# ATMEGA2560-Schematic.net
KiCad netlist of a schematic drawn in Altium Designer
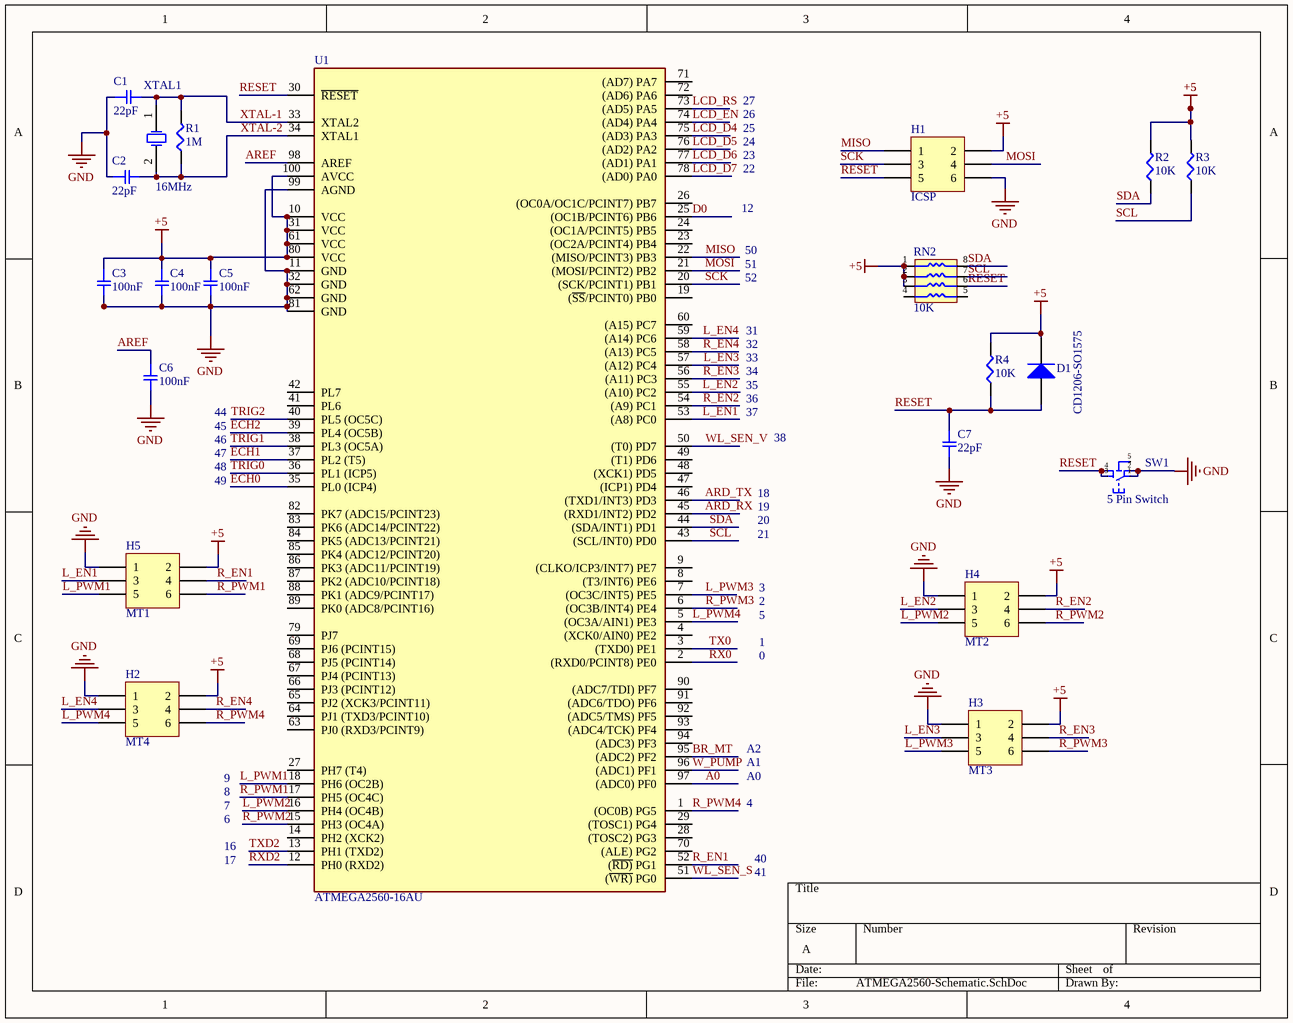
[diagram p0: ATMEGA2560-Schematic.SchDoc]

(export (version "E")
  (design (tool "Eeschema 10.0.6"))
  (components
    (comp (ref "C1")
      (value "22pF")
      (description "CAP CER 10000PF 250V X7T 0805")
      (fields
        (field (name "DIGI-KEY PART NUMBER") "490-13986-1-ND")
        (field (name "PART NUMBER") "GC321AD72E103KX01D")
      )
      (libsource (lib "capacitor0805") (part "GC321AD72E103KX01D"))
    )
    (comp (ref "C2")
      (value "22pF")
      (description "CAP CER 10000PF 250V X7T 0805")
      (fields
        (field (name "DIGI-KEY PART NUMBER") "490-13986-1-ND")
        (field (name "PART NUMBER") "GC321AD72E103KX01D")
      )
      (libsource (lib "capacitor0805") (part "GC321AD72E103KX01D"))
    )
    (comp (ref "C3")
      (value "100nF")
      (footprint "SMD-0805C")
      (description "CAP CER 10000PF 250V X7T 0805")
      (fields
        (field (name "DIGI-KEY PART NUMBER") "490-13986-1-ND")
        (field (name "PART NUMBER") "GC321AD72E103KX01D")
      )
      (libsource (lib "capacitor0805") (part "GC321AD72E103KX01D"))
    )
    (comp (ref "C4")
      (value "100nF")
      (footprint "SMD-0805C")
      (description "CAP CER 10000PF 250V X7T 0805")
      (fields
        (field (name "DIGI-KEY PART NUMBER") "490-13986-1-ND")
        (field (name "PART NUMBER") "GC321AD72E103KX01D")
      )
      (libsource (lib "capacitor0805") (part "GC321AD72E103KX01D"))
    )
    (comp (ref "C5")
      (value "100nF")
      (footprint "SMD-0805C")
      (description "CAP CER 10000PF 250V X7T 0805")
      (fields
        (field (name "DIGI-KEY PART NUMBER") "490-13986-1-ND")
        (field (name "PART NUMBER") "GC321AD72E103KX01D")
      )
      (libsource (lib "capacitor0805") (part "GC321AD72E103KX01D"))
    )
    (comp (ref "C6")
      (value "100nF")
      (footprint "SMD-0805C")
      (description "CAP CER 10000PF 250V X7T 0805")
      (fields
        (field (name "DIGI-KEY PART NUMBER") "490-13986-1-ND")
        (field (name "PART NUMBER") "GC321AD72E103KX01D")
      )
      (libsource (lib "capacitor0805") (part "GC321AD72E103KX01D"))
    )
    (comp (ref "C7")
      (value "22pF")
      (footprint "SMD-0603C")
      (description "CAP CER 10000PF 250V X7T 0805")
      (fields
        (field (name "DIGI-KEY PART NUMBER") "490-13986-1-ND")
        (field (name "PART NUMBER") "GC321AD72E103KX01D")
      )
      (libsource (lib "capacitor0805") (part "GC321AD72E103KX01D"))
    )
    (comp (ref "D1")
      (value "CD1206-SO1575")
      (footprint "D1206-RD")
      (description "Default Diode")
      (fields (field (name "PUBLISHER") "Altium Limited"))
      (libsource (lib "Miscellaneous Devices") (part "Diode"))
    )
    (comp (ref "H1")
      (value "ICSP")
      (footprint "HDR2X3")
      (description "Header, 3-Pin, Dual row")
      (fields (field (name "PUBLISHER") "Altium Limited"))
      (libsource (lib "Miscellaneous Connectors") (part "Header 3X2"))
    )
    (comp (ref "H2")
      (value "MT4")
      (footprint "HDR2X3")
      (description "Header, 3-Pin, Dual row")
      (fields (field (name "PUBLISHER") "Altium Limited"))
      (libsource (lib "Miscellaneous Connectors") (part "Header 3X2"))
    )
    (comp (ref "H3")
      (value "MT3")
      (footprint "HDR2X3")
      (description "Header, 3-Pin, Dual row")
      (fields (field (name "PUBLISHER") "Altium Limited"))
      (libsource (lib "Miscellaneous Connectors") (part "Header 3X2"))
    )
    (comp (ref "H4")
      (value "MT2")
      (footprint "HDR2X3")
      (description "Header, 3-Pin, Dual row")
      (fields (field (name "PUBLISHER") "Altium Limited"))
      (libsource (lib "Miscellaneous Connectors") (part "Header 3X2"))
    )
    (comp (ref "H5")
      (value "MT1")
      (footprint "HDR2X3")
      (description "Header, 3-Pin, Dual row")
      (fields (field (name "PUBLISHER") "Altium Limited"))
      (libsource (lib "Miscellaneous Connectors") (part "Header 3X2"))
    )
    (comp (ref "R1")
      (value "1M")
      (footprint "SMD-0805-RES")
      (description "RES SMD 1.1 OHM 1% 1/3W 0805")
      (fields (field (name "PART NUMBER") "ERJ-6BQF1R1V") (field (name "DIGI-KEY PART NUMBER") "P17500CT-ND"))
      (libsource (lib "Res0805") (part "ERJ-6BQF1R1V"))
    )
    (comp (ref "R2")
      (value "10K")
      (description "RES SMD 1.1 OHM 1% 1/3W 0805")
      (fields (field (name "PART NUMBER") "ERJ-6BQF1R1V") (field (name "DIGI-KEY PART NUMBER") "P17500CT-ND"))
      (libsource (lib "Res0805") (part "ERJ-6BQF1R1V"))
    )
    (comp (ref "R3")
      (value "10K")
      (description "RES SMD 1.1 OHM 1% 1/3W 0805")
      (fields (field (name "PART NUMBER") "ERJ-6BQF1R1V") (field (name "DIGI-KEY PART NUMBER") "P17500CT-ND"))
      (libsource (lib "Res0805") (part "ERJ-6BQF1R1V"))
    )
    (comp (ref "R4")
      (value "10K")
      (description "RES SMD 1.1 OHM 1% 1/3W 0805")
      (fields (field (name "PART NUMBER") "ERJ-6BQF1R1V") (field (name "DIGI-KEY PART NUMBER") "P17500CT-ND"))
      (libsource (lib "Res0805") (part "ERJ-6BQF1R1V"))
    )
    (comp (ref "RN2")
      (value "10K")
      (footprint "RA0603-8")
      (fields (field (name "MF") "Yageo") (field (name "MP") "YC164-JR-07330RL"))
      (libsource (lib "ResNetwork(SMD)") (part "RES_NETWORK"))
    )
    (comp (ref "SW1")
      (value "5 Pin Switch")
      (footprint "SPDT-5Pin")
      (libsource (lib "SPDT-SW") (part "SPDT-SWITCH"))
    )
    (comp (ref "U1")
      (value "ATMEGA2560-16AU")
      (footprint "TQFP-100(LCSC)")
      (description "Integrated Circuit")
      (libsource (lib "ATMEGA2560-16AU") (part "ATMEGA2560-16AU (LCSC)"))
    )
    (comp (ref "XTAL1")
      (value "16MHz")
      (description "Crystal Oscillator")
      (fields (field (name "PUBLISHER") "Altium Limited"))
      (libsource (lib "XTAL_Generic") (part "Crystal Oscillator"))
    )
  )
  (nets
    (net (code "1") (name "+5") (class "Default")
      (node (ref "C3") (pin "1") (pinfunction "1_1") (pintype "passive"))
      (node (ref "C4") (pin "1") (pinfunction "1_1") (pintype "passive"))
      (node (ref "C5") (pin "1") (pinfunction "1_1") (pintype "passive"))
      (node (ref "D1") (pin "2") (pinfunction "K_2") (pintype "passive"))
      (node (ref "H1") (pin "2") (pinfunction "2_2") (pintype "passive"))
      (node (ref "H2") (pin "2") (pinfunction "2_2") (pintype "passive"))
      (node (ref "H3") (pin "2") (pinfunction "2_2") (pintype "passive"))
      (node (ref "H4") (pin "2") (pinfunction "2_2") (pintype "passive"))
      (node (ref "H5") (pin "2") (pinfunction "2_2") (pintype "passive"))
      (node (ref "R2") (pin "2") (pinfunction "2_2") (pintype "passive"))
      (node (ref "R3") (pin "2") (pinfunction "2_2") (pintype "passive"))
      (node (ref "R4") (pin "2") (pinfunction "2_2") (pintype "passive"))
      (node (ref "RN2") (pin "1") (pinfunction "1_1") (pintype "passive"))
      (node (ref "RN2") (pin "2") (pinfunction "2_2") (pintype "passive"))
      (node (ref "RN2") (pin "3") (pinfunction "3_3") (pintype "passive"))
      (node (ref "U1") (pin "10") (pinfunction "VCC_10") (pintype "passive"))
      (node (ref "U1") (pin "100") (pinfunction "AVCC_100") (pintype "passive"))
      (node (ref "U1") (pin "31") (pinfunction "VCC_31") (pintype "passive"))
      (node (ref "U1") (pin "61") (pinfunction "VCC_61") (pintype "passive"))
      (node (ref "U1") (pin "80") (pinfunction "VCC_80") (pintype "passive"))
    )
    (net (code "2") (name "/A0") (class "Default")
      (node (ref "U1") (pin "97") (pinfunction "(ADC0)_PF0_97") (pintype "passive"))
    )
    (net (code "3") (name "/ARD_RX") (class "Default")
      (node (ref "U1") (pin "45") (pinfunction "(RXD1/INT2)_PD2_45") (pintype "passive"))
    )
    (net (code "4") (name "/ARD_TX") (class "Default")
      (node (ref "U1") (pin "46") (pinfunction "(TXD1/INT3)_PD3_46") (pintype "passive"))
    )
    (net (code "5") (name "/AREF") (class "Default")
      (node (ref "C6") (pin "1") (pinfunction "1_1") (pintype "passive"))
      (node (ref "U1") (pin "98") (pinfunction "AREF_98") (pintype "passive"))
    )
    (net (code "6") (name "/BR_MT") (class "Default")
      (node (ref "U1") (pin "95") (pinfunction "(ADC2)_PF2_95") (pintype "passive"))
    )
    (net (code "7") (name "/D0") (class "Default")
      (node (ref "U1") (pin "25") (pinfunction "(OC1B/PCINT6)_PB6_25") (pintype "passive"))
    )
    (net (code "8") (name "/ECH0") (class "Default")
      (node (ref "U1") (pin "35") (pinfunction "PL0_(ICP4)_35") (pintype "passive"))
    )
    (net (code "9") (name "/ECH1") (class "Default")
      (node (ref "U1") (pin "37") (pinfunction "PL2_(T5)_37") (pintype "passive"))
    )
    (net (code "10") (name "/ECH2") (class "Default")
      (node (ref "U1") (pin "39") (pinfunction "PL4_(OC5B)_39") (pintype "passive"))
    )
    (net (code "11") (name "/LCD_D4") (class "Default")
      (node (ref "U1") (pin "75") (pinfunction "(AD3)_PA3_75") (pintype "passive"))
    )
    (net (code "12") (name "/LCD_D5") (class "Default")
      (node (ref "U1") (pin "76") (pinfunction "(AD2)_PA2_76") (pintype "passive"))
    )
    (net (code "13") (name "/LCD_D6") (class "Default")
      (node (ref "U1") (pin "77") (pinfunction "(AD1)_PA1_77") (pintype "passive"))
    )
    (net (code "14") (name "/LCD_D7") (class "Default")
      (node (ref "U1") (pin "78") (pinfunction "(AD0)_PA0_78") (pintype "passive"))
    )
    (net (code "15") (name "/LCD_EN") (class "Default")
      (node (ref "U1") (pin "74") (pinfunction "(AD4)_PA4_74") (pintype "passive"))
    )
    (net (code "16") (name "/LCD_RS") (class "Default")
      (node (ref "U1") (pin "73") (pinfunction "(AD5)_PA5_73") (pintype "passive"))
    )
    (net (code "17") (name "/L_EN1") (class "Default")
      (node (ref "H5") (pin "3") (pinfunction "3_3") (pintype "passive"))
      (node (ref "U1") (pin "53") (pinfunction "(A8)_PC0_53") (pintype "passive"))
    )
    (net (code "18") (name "/L_EN2") (class "Default")
      (node (ref "H4") (pin "3") (pinfunction "3_3") (pintype "passive"))
      (node (ref "U1") (pin "55") (pinfunction "(A10)_PC2_55") (pintype "passive"))
    )
    (net (code "19") (name "/L_EN3") (class "Default")
      (node (ref "H3") (pin "3") (pinfunction "3_3") (pintype "passive"))
      (node (ref "U1") (pin "57") (pinfunction "(A12)_PC4_57") (pintype "passive"))
    )
    (net (code "20") (name "/L_EN4") (class "Default")
      (node (ref "H2") (pin "3") (pinfunction "3_3") (pintype "passive"))
      (node (ref "U1") (pin "59") (pinfunction "(A14)_PC6_59") (pintype "passive"))
    )
    (net (code "21") (name "/L_PWM1") (class "Default")
      (node (ref "H5") (pin "5") (pinfunction "5_5") (pintype "passive"))
      (node (ref "U1") (pin "18") (pinfunction "PH6_(OC2B)_18") (pintype "passive"))
    )
    (net (code "22") (name "/L_PWM2") (class "Default")
      (node (ref "H4") (pin "5") (pinfunction "5_5") (pintype "passive"))
      (node (ref "U1") (pin "16") (pinfunction "PH4_(OC4B)_16") (pintype "passive"))
    )
    (net (code "23") (name "/L_PWM3") (class "Default")
      (node (ref "H3") (pin "5") (pinfunction "5_5") (pintype "passive"))
      (node (ref "U1") (pin "7") (pinfunction "(OC3C/INT5)_PE5_7") (pintype "passive"))
    )
    (net (code "24") (name "/L_PWM4") (class "Default")
      (node (ref "H2") (pin "5") (pinfunction "5_5") (pintype "passive"))
      (node (ref "U1") (pin "5") (pinfunction "(OC3A/AIN1)_PE3_5") (pintype "passive"))
    )
    (net (code "25") (name "/MISO") (class "Default")
      (node (ref "H1") (pin "1") (pinfunction "1_1") (pintype "passive"))
      (node (ref "U1") (pin "22") (pinfunction "(MISO/PCINT3)_PB3_22") (pintype "passive"))
    )
    (net (code "26") (name "/MOSI") (class "Default")
      (node (ref "H1") (pin "4") (pinfunction "4_4") (pintype "passive"))
      (node (ref "U1") (pin "21") (pinfunction "(MOSI/PCINT2)_PB2_21") (pintype "passive"))
    )
    (net (code "27") (name "/RESET") (class "Default")
      (node (ref "C7") (pin "1") (pinfunction "1_1") (pintype "passive"))
      (node (ref "D1") (pin "1") (pinfunction "A_1") (pintype "passive"))
      (node (ref "H1") (pin "5") (pinfunction "5_5") (pintype "passive"))
      (node (ref "R4") (pin "1") (pinfunction "1_1") (pintype "passive"))
      (node (ref "RN2") (pin "6") (pinfunction "6_6") (pintype "passive"))
      (node (ref "SW1") (pin "3") (pinfunction "3_3") (pintype "passive"))
      (node (ref "SW1") (pin "4") (pinfunction "4_4") (pintype "passive"))
      (node (ref "U1") (pin "30") (pinfunction "~{RESET}_30") (pintype "passive"))
    )
    (net (code "28") (name "/RX0") (class "Default")
      (node (ref "U1") (pin "2") (pinfunction "(RXD0/PCINT8)_PE0_2") (pintype "passive"))
    )
    (net (code "29") (name "/RXD2") (class "Default")
      (node (ref "U1") (pin "12") (pinfunction "PH0_(RXD2)_12") (pintype "passive"))
    )
    (net (code "30") (name "/R_EN1") (class "Default")
      (node (ref "H5") (pin "4") (pinfunction "4_4") (pintype "passive"))
      (node (ref "U1") (pin "52") (pinfunction "(~{RD)}_PG1_52") (pintype "passive"))
    )
    (net (code "31") (name "/R_EN2") (class "Default")
      (node (ref "H4") (pin "4") (pinfunction "4_4") (pintype "passive"))
      (node (ref "U1") (pin "54") (pinfunction "(A9)_PC1_54") (pintype "passive"))
    )
    (net (code "32") (name "/R_EN3") (class "Default")
      (node (ref "H3") (pin "4") (pinfunction "4_4") (pintype "passive"))
      (node (ref "U1") (pin "56") (pinfunction "(A11)_PC3_56") (pintype "passive"))
    )
    (net (code "33") (name "/R_EN4") (class "Default")
      (node (ref "H2") (pin "4") (pinfunction "4_4") (pintype "passive"))
      (node (ref "U1") (pin "58") (pinfunction "(A13)_PC5_58") (pintype "passive"))
    )
    (net (code "34") (name "/R_PWM1") (class "Default")
      (node (ref "H5") (pin "6") (pinfunction "6_6") (pintype "passive"))
      (node (ref "U1") (pin "17") (pinfunction "PH5_(OC4C)_17") (pintype "passive"))
    )
    (net (code "35") (name "/R_PWM2") (class "Default")
      (node (ref "H4") (pin "6") (pinfunction "6_6") (pintype "passive"))
      (node (ref "U1") (pin "15") (pinfunction "PH3_(OC4A)_15") (pintype "passive"))
    )
    (net (code "36") (name "/R_PWM3") (class "Default")
      (node (ref "H3") (pin "6") (pinfunction "6_6") (pintype "passive"))
      (node (ref "U1") (pin "6") (pinfunction "(OC3B/INT4)_PE4_6") (pintype "passive"))
    )
    (net (code "37") (name "/R_PWM4") (class "Default")
      (node (ref "H2") (pin "6") (pinfunction "6_6") (pintype "passive"))
      (node (ref "U1") (pin "1") (pinfunction "(OC0B)_PG5_1") (pintype "passive"))
    )
    (net (code "38") (name "/SCK") (class "Default")
      (node (ref "H1") (pin "3") (pinfunction "3_3") (pintype "passive"))
      (node (ref "U1") (pin "20") (pinfunction "(SCK/PCINT1)_PB1_20") (pintype "passive"))
    )
    (net (code "39") (name "/SCL") (class "Default")
      (node (ref "R3") (pin "1") (pinfunction "1_1") (pintype "passive"))
      (node (ref "RN2") (pin "7") (pinfunction "7_7") (pintype "passive"))
      (node (ref "U1") (pin "43") (pinfunction "(SCL/INT0)_PD0_43") (pintype "passive"))
    )
    (net (code "40") (name "/SDA") (class "Default")
      (node (ref "R2") (pin "1") (pinfunction "1_1") (pintype "passive"))
      (node (ref "RN2") (pin "8") (pinfunction "8_8") (pintype "passive"))
      (node (ref "U1") (pin "44") (pinfunction "(SDA/INT1)_PD1_44") (pintype "passive"))
    )
    (net (code "41") (name "/TRIG0") (class "Default")
      (node (ref "U1") (pin "36") (pinfunction "PL1_(ICP5)_36") (pintype "passive"))
    )
    (net (code "42") (name "/TRIG1") (class "Default")
      (node (ref "U1") (pin "38") (pinfunction "PL3_(OC5A)_38") (pintype "passive"))
    )
    (net (code "43") (name "/TRIG2") (class "Default")
      (node (ref "U1") (pin "40") (pinfunction "PL5_(OC5C)_40") (pintype "passive"))
    )
    (net (code "44") (name "/TX0") (class "Default")
      (node (ref "U1") (pin "3") (pinfunction "(TXD0)_PE1_3") (pintype "passive"))
    )
    (net (code "45") (name "/TXD2") (class "Default")
      (node (ref "U1") (pin "13") (pinfunction "PH1_(TXD2)_13") (pintype "passive"))
    )
    (net (code "46") (name "/WL_SEN_S") (class "Default")
      (node (ref "U1") (pin "51") (pinfunction "(~{WR)}_PG0_51") (pintype "passive"))
    )
    (net (code "47") (name "/WL_SEN_V") (class "Default")
      (node (ref "U1") (pin "50") (pinfunction "(T0)_PD7_50") (pintype "passive"))
    )
    (net (code "48") (name "/W_PUMP") (class "Default")
      (node (ref "U1") (pin "96") (pinfunction "(ADC1)_PF1_96") (pintype "passive"))
    )
    (net (code "49") (name "/XTAL-1") (class "Default")
      (node (ref "C1") (pin "2") (pinfunction "2_2") (pintype "passive"))
      (node (ref "R1") (pin "2") (pinfunction "2_2") (pintype "passive"))
      (node (ref "U1") (pin "33") (pinfunction "XTAL2_33") (pintype "passive"))
      (node (ref "XTAL1") (pin "1") (pinfunction "OSC1_1") (pintype "passive"))
    )
    (net (code "50") (name "/XTAL-2") (class "Default")
      (node (ref "C2") (pin "2") (pinfunction "2_2") (pintype "passive"))
      (node (ref "R1") (pin "1") (pinfunction "1_1") (pintype "passive"))
      (node (ref "U1") (pin "34") (pinfunction "XTAL1_34") (pintype "passive"))
      (node (ref "XTAL1") (pin "2") (pinfunction "OSC2_2") (pintype "passive"))
    )
    (net (code "51") (name "GND") (class "Default")
      (node (ref "C1") (pin "1") (pinfunction "1_1") (pintype "passive"))
      (node (ref "C2") (pin "1") (pinfunction "1_1") (pintype "passive"))
      (node (ref "C3") (pin "2") (pinfunction "2_2") (pintype "passive"))
      (node (ref "C4") (pin "2") (pinfunction "2_2") (pintype "passive"))
      (node (ref "C5") (pin "2") (pinfunction "2_2") (pintype "passive"))
      (node (ref "C6") (pin "2") (pinfunction "2_2") (pintype "passive"))
      (node (ref "C7") (pin "2") (pinfunction "2_2") (pintype "passive"))
      (node (ref "H1") (pin "6") (pinfunction "6_6") (pintype "passive"))
      (node (ref "H2") (pin "1") (pinfunction "1_1") (pintype "passive"))
      (node (ref "H3") (pin "1") (pinfunction "1_1") (pintype "passive"))
      (node (ref "H4") (pin "1") (pinfunction "1_1") (pintype "passive"))
      (node (ref "H5") (pin "1") (pinfunction "1_1") (pintype "passive"))
      (node (ref "SW1") (pin "1") (pinfunction "1_1") (pintype "passive"))
      (node (ref "SW1") (pin "2") (pinfunction "2_2") (pintype "passive"))
      (node (ref "U1") (pin "11") (pinfunction "GND_11") (pintype "passive"))
      (node (ref "U1") (pin "32") (pinfunction "GND_32") (pintype "passive"))
      (node (ref "U1") (pin "62") (pinfunction "GND_62") (pintype "passive"))
      (node (ref "U1") (pin "81") (pinfunction "GND_81") (pintype "passive"))
      (node (ref "U1") (pin "99") (pinfunction "AGND_99") (pintype "passive"))
    )
    (net (code "52") (name "unconnected-(RN2-Pad4)") (class "Default")
      (node (ref "RN2") (pin "4") (pinfunction "4_4") (pintype "passive"))
    )
    (net (code "53") (name "unconnected-(RN2-Pad5)") (class "Default")
      (node (ref "RN2") (pin "5") (pinfunction "5_5") (pintype "passive"))
    )
    (net (code "54") (name "unconnected-(SW1-Pad5)") (class "Default")
      (node (ref "SW1") (pin "5") (pinfunction "5_5") (pintype "passive"))
    )
    (net (code "55") (name "unconnected-(U1-(A15)_PC7-Pad60)") (class "Default")
      (node (ref "U1") (pin "60") (pinfunction "(A15)_PC7_60") (pintype "passive"))
    )
    (net (code "56") (name "unconnected-(U1-(AD6)_PA6-Pad72)") (class "Default")
      (node (ref "U1") (pin "72") (pinfunction "(AD6)_PA6_72") (pintype "passive"))
    )
    (net (code "57") (name "unconnected-(U1-(AD7)_PA7-Pad71)") (class "Default")
      (node (ref "U1") (pin "71") (pinfunction "(AD7)_PA7_71") (pintype "passive"))
    )
    (net (code "58") (name "unconnected-(U1-(ADC3)_PF3-Pad94)") (class "Default")
      (node (ref "U1") (pin "94") (pinfunction "(ADC3)_PF3_94") (pintype "passive"))
    )
    (net (code "59") (name "unconnected-(U1-(ADC4{slash}TCK)_PF4-Pad93)") (class "Default")
      (node (ref "U1") (pin "93") (pinfunction "(ADC4/TCK)_PF4_93") (pintype "passive"))
    )
    (net (code "60") (name "unconnected-(U1-(ADC5{slash}TMS)_PF5-Pad92)") (class "Default")
      (node (ref "U1") (pin "92") (pinfunction "(ADC5/TMS)_PF5_92") (pintype "passive"))
    )
    (net (code "61") (name "unconnected-(U1-(ADC6{slash}TDO)_PF6-Pad91)") (class "Default")
      (node (ref "U1") (pin "91") (pinfunction "(ADC6/TDO)_PF6_91") (pintype "passive"))
    )
    (net (code "62") (name "unconnected-(U1-(ADC7{slash}TDI)_PF7-Pad90)") (class "Default")
      (node (ref "U1") (pin "90") (pinfunction "(ADC7/TDI)_PF7_90") (pintype "passive"))
    )
    (net (code "63") (name "unconnected-(U1-(ALE)_PG2-Pad70)") (class "Default")
      (node (ref "U1") (pin "70") (pinfunction "(ALE)_PG2_70") (pintype "passive"))
    )
    (net (code "64") (name "unconnected-(U1-(CLKO{slash}ICP3{slash}INT7)_PE7-Pad9)") (class "Default")
      (node (ref "U1") (pin "9") (pinfunction "(CLKO/ICP3/INT7)_PE7_9") (pintype "passive"))
    )
    (net (code "65") (name "unconnected-(U1-(ICP1)_PD4-Pad47)") (class "Default")
      (node (ref "U1") (pin "47") (pinfunction "(ICP1)_PD4_47") (pintype "passive"))
    )
    (net (code "66") (name "unconnected-(U1-(OC0A{slash}OC1C{slash}PCINT7)_PB7-Pad26)") (class "Default")
      (node (ref "U1") (pin "26") (pinfunction "(OC0A/OC1C/PCINT7)_PB7_26") (pintype "passive"))
    )
    (net (code "67") (name "unconnected-(U1-(OC1A{slash}PCINT5)_PB5-Pad24)") (class "Default")
      (node (ref "U1") (pin "24") (pinfunction "(OC1A/PCINT5)_PB5_24") (pintype "passive"))
    )
    (net (code "68") (name "unconnected-(U1-(OC2A{slash}PCINT4)_PB4-Pad23)") (class "Default")
      (node (ref "U1") (pin "23") (pinfunction "(OC2A/PCINT4)_PB4_23") (pintype "passive"))
    )
    (net (code "69") (name "unconnected-(U1-(T1)_PD6-Pad49)") (class "Default")
      (node (ref "U1") (pin "49") (pinfunction "(T1)_PD6_49") (pintype "passive"))
    )
    (net (code "70") (name "unconnected-(U1-(T3{slash}INT6)_PE6-Pad8)") (class "Default")
      (node (ref "U1") (pin "8") (pinfunction "(T3/INT6)_PE6_8") (pintype "passive"))
    )
    (net (code "71") (name "unconnected-(U1-(TOSC1)_PG4-Pad29)") (class "Default")
      (node (ref "U1") (pin "29") (pinfunction "(TOSC1)_PG4_29") (pintype "passive"))
    )
    (net (code "72") (name "unconnected-(U1-(TOSC2)_PG3-Pad28)") (class "Default")
      (node (ref "U1") (pin "28") (pinfunction "(TOSC2)_PG3_28") (pintype "passive"))
    )
    (net (code "73") (name "unconnected-(U1-(XCK0{slash}AIN0)_PE2-Pad4)") (class "Default")
      (node (ref "U1") (pin "4") (pinfunction "(XCK0/AIN0)_PE2_4") (pintype "passive"))
    )
    (net (code "74") (name "unconnected-(U1-(XCK1)_PD5-Pad48)") (class "Default")
      (node (ref "U1") (pin "48") (pinfunction "(XCK1)_PD5_48") (pintype "passive"))
    )
    (net (code "75") (name "unconnected-(U1-(~{SS}{slash}PCINT0)_PB0-Pad19)") (class "Default")
      (node (ref "U1") (pin "19") (pinfunction "(~{SS}/PCINT0)_PB0_19") (pintype "passive"))
    )
    (net (code "76") (name "unconnected-(U1-PH2_(XCK2)-Pad14)") (class "Default")
      (node (ref "U1") (pin "14") (pinfunction "PH2_(XCK2)_14") (pintype "passive"))
    )
    (net (code "77") (name "unconnected-(U1-PH7_(T4)-Pad27)") (class "Default")
      (node (ref "U1") (pin "27") (pinfunction "PH7_(T4)_27") (pintype "passive"))
    )
    (net (code "78") (name "unconnected-(U1-PJ0_(RXD3{slash}PCINT9)-Pad63)") (class "Default")
      (node (ref "U1") (pin "63") (pinfunction "PJ0_(RXD3/PCINT9)_63") (pintype "passive"))
    )
    (net (code "79") (name "unconnected-(U1-PJ1_(TXD3{slash}PCINT10)-Pad64)") (class "Default")
      (node (ref "U1") (pin "64") (pinfunction "PJ1_(TXD3/PCINT10)_64") (pintype "passive"))
    )
    (net (code "80") (name "unconnected-(U1-PJ2_(XCK3{slash}PCINT11)-Pad65)") (class "Default")
      (node (ref "U1") (pin "65") (pinfunction "PJ2_(XCK3/PCINT11)_65") (pintype "passive"))
    )
    (net (code "81") (name "unconnected-(U1-PJ3_(PCINT12)-Pad66)") (class "Default")
      (node (ref "U1") (pin "66") (pinfunction "PJ3_(PCINT12)_66") (pintype "passive"))
    )
    (net (code "82") (name "unconnected-(U1-PJ4_(PCINT13)-Pad67)") (class "Default")
      (node (ref "U1") (pin "67") (pinfunction "PJ4_(PCINT13)_67") (pintype "passive"))
    )
    (net (code "83") (name "unconnected-(U1-PJ5_(PCINT14)-Pad68)") (class "Default")
      (node (ref "U1") (pin "68") (pinfunction "PJ5_(PCINT14)_68") (pintype "passive"))
    )
    (net (code "84") (name "unconnected-(U1-PJ6_(PCINT15)-Pad69)") (class "Default")
      (node (ref "U1") (pin "69") (pinfunction "PJ6_(PCINT15)_69") (pintype "passive"))
    )
    (net (code "85") (name "unconnected-(U1-PJ7-Pad79)") (class "Default")
      (node (ref "U1") (pin "79") (pinfunction "PJ7_79") (pintype "passive"))
    )
    (net (code "86") (name "unconnected-(U1-PK0_(ADC8{slash}PCINT16)-Pad89)") (class "Default")
      (node (ref "U1") (pin "89") (pinfunction "PK0_(ADC8/PCINT16)_89") (pintype "passive"))
    )
    (net (code "87") (name "unconnected-(U1-PK1_(ADC9{slash}PCINT17)-Pad88)") (class "Default")
      (node (ref "U1") (pin "88") (pinfunction "PK1_(ADC9/PCINT17)_88") (pintype "passive"))
    )
    (net (code "88") (name "unconnected-(U1-PK2_(ADC10{slash}PCINT18)-Pad87)") (class "Default")
      (node (ref "U1") (pin "87") (pinfunction "PK2_(ADC10/PCINT18)_87") (pintype "passive"))
    )
    (net (code "89") (name "unconnected-(U1-PK3_(ADC11{slash}PCINT19)-Pad86)") (class "Default")
      (node (ref "U1") (pin "86") (pinfunction "PK3_(ADC11/PCINT19)_86") (pintype "passive"))
    )
    (net (code "90") (name "unconnected-(U1-PK4_(ADC12{slash}PCINT20)-Pad85)") (class "Default")
      (node (ref "U1") (pin "85") (pinfunction "PK4_(ADC12/PCINT20)_85") (pintype "passive"))
    )
    (net (code "91") (name "unconnected-(U1-PK5_(ADC13{slash}PCINT21)-Pad84)") (class "Default")
      (node (ref "U1") (pin "84") (pinfunction "PK5_(ADC13/PCINT21)_84") (pintype "passive"))
    )
    (net (code "92") (name "unconnected-(U1-PK6_(ADC14{slash}PCINT22)-Pad83)") (class "Default")
      (node (ref "U1") (pin "83") (pinfunction "PK6_(ADC14/PCINT22)_83") (pintype "passive"))
    )
    (net (code "93") (name "unconnected-(U1-PK7_(ADC15{slash}PCINT23)-Pad82)") (class "Default")
      (node (ref "U1") (pin "82") (pinfunction "PK7_(ADC15/PCINT23)_82") (pintype "passive"))
    )
    (net (code "94") (name "unconnected-(U1-PL6-Pad41)") (class "Default")
      (node (ref "U1") (pin "41") (pinfunction "PL6_41") (pintype "passive"))
    )
    (net (code "95") (name "unconnected-(U1-PL7-Pad42)") (class "Default")
      (node (ref "U1") (pin "42") (pinfunction "PL7_42") (pintype "passive"))
    )
  )
)
